# STPedal_Peripherals.net
KiCad netlist of a schematic drawn in Altium Designer
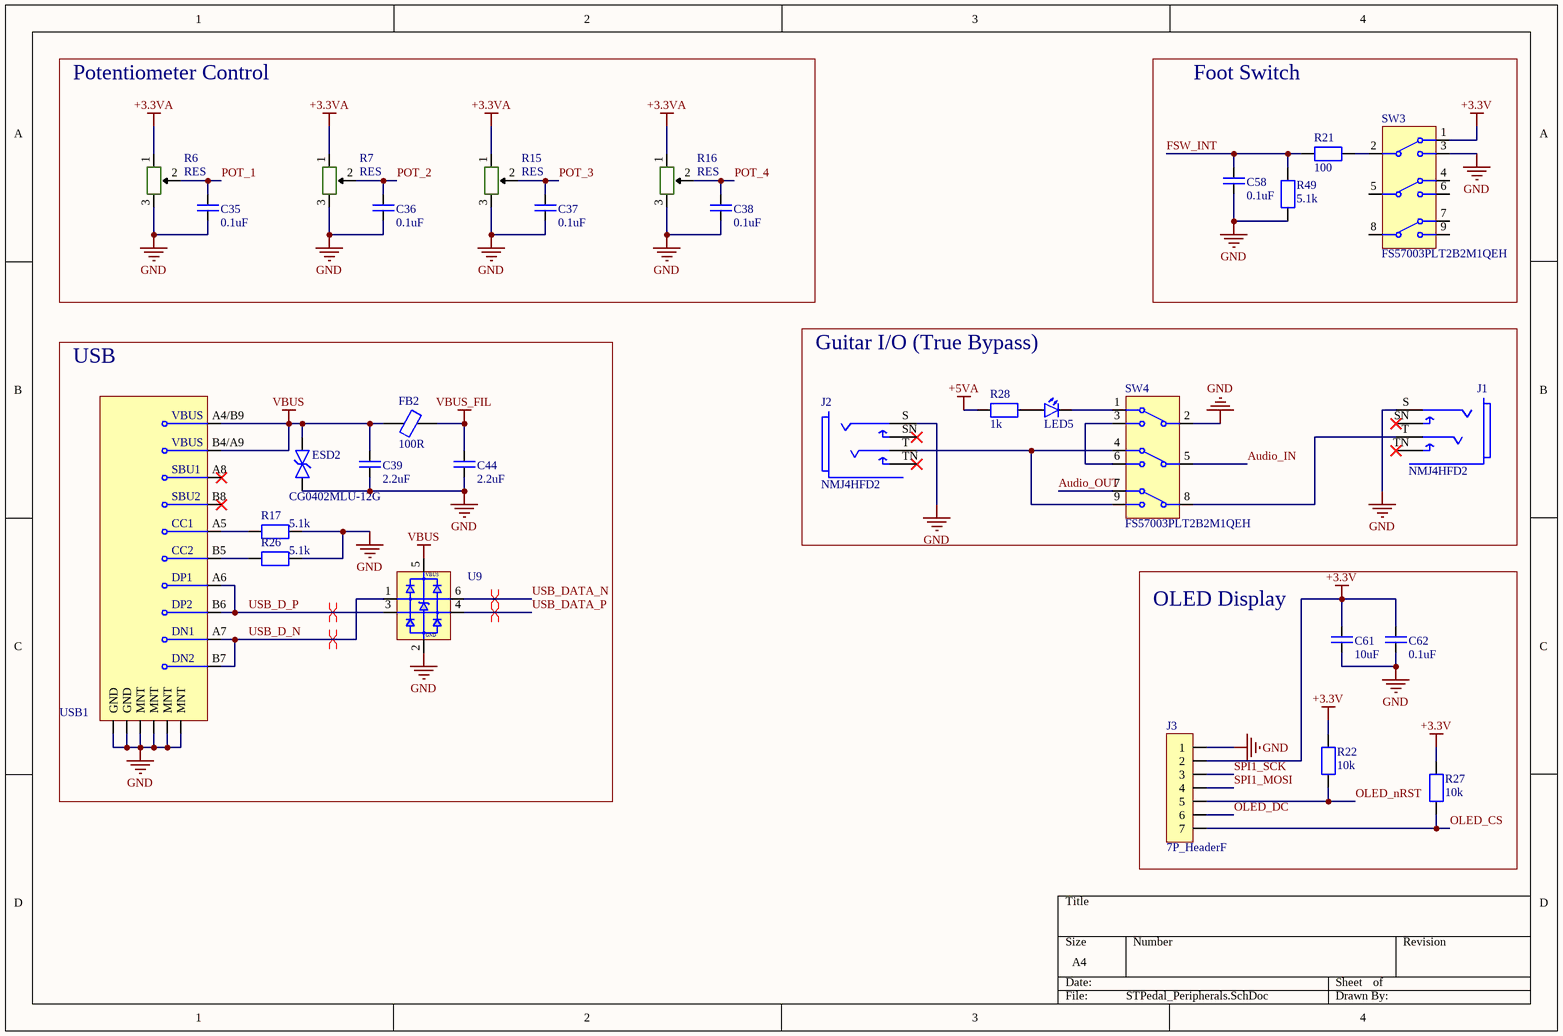
[diagram p0: STPedal_Peripherals.SchDoc]

(export (version "E")
  (design (tool "Eeschema 10.0.6"))
  (components
    (comp (ref "C35")
      (value "0.1uF")
      (footprint "CAPC_0402_1005X55N")
      (description "Capacitor 0402 - 0.1uF +-/10% / 16V")
      (fields
        (field (name "MANUFACTURER") "Samsung Electro-Mechanics")
        (field (name "MPN") "CL05B104KO5NNNC")
      )
      (libsource (lib "ReekoLib") (part "0.1uF_CAP_0402"))
    )
    (comp (ref "C36")
      (value "0.1uF")
      (footprint "CAPC_0402_1005X55N")
      (description "Capacitor 0402 - 0.1uF +-/10% / 16V")
      (fields
        (field (name "MANUFACTURER") "Samsung Electro-Mechanics")
        (field (name "MPN") "CL05B104KO5NNNC")
      )
      (libsource (lib "ReekoLib") (part "0.1uF_CAP_0402"))
    )
    (comp (ref "C37")
      (value "0.1uF")
      (footprint "CAPC_0402_1005X55N")
      (description "Capacitor 0402 - 0.1uF +-/10% / 16V")
      (fields
        (field (name "MANUFACTURER") "Samsung Electro-Mechanics")
        (field (name "MPN") "CL05B104KO5NNNC")
      )
      (libsource (lib "ReekoLib") (part "0.1uF_CAP_0402"))
    )
    (comp (ref "C38")
      (value "0.1uF")
      (footprint "CAPC_0402_1005X55N")
      (description "Capacitor 0402 - 0.1uF +-/10% / 16V")
      (fields
        (field (name "MANUFACTURER") "Samsung Electro-Mechanics")
        (field (name "MPN") "CL05B104KO5NNNC")
      )
      (libsource (lib "ReekoLib") (part "0.1uF_CAP_0402"))
    )
    (comp (ref "C39")
      (value "2.2uF")
      (footprint "CAPC_0402_1005X55N")
      (description "Capacitor 0402 - 2.2uF +-/10% / 25V")
      (fields
        (field (name "MANUFACTURER") "Samsung Electro-Mechanics")
        (field (name "MPN") "CL05A225MQ5NSNC")
      )
      (libsource (lib "ReekoLib") (part "2.2uF_CAP_0402"))
    )
    (comp (ref "C44")
      (value "2.2uF")
      (footprint "CAPC_0402_1005X55N")
      (description "Capacitor 0402 - 2.2uF +-/10% / 25V")
      (fields
        (field (name "MANUFACTURER") "Samsung Electro-Mechanics")
        (field (name "MPN") "CL05A225MQ5NSNC")
      )
      (libsource (lib "ReekoLib") (part "2.2uF_CAP_0402"))
    )
    (comp (ref "C58")
      (value "0.1uF")
      (footprint "CAPC_0402_1005X55N")
      (description "Capacitor 0402 - 0.1uF +-/10% / 16V")
      (fields
        (field (name "MANUFACTURER") "Samsung Electro-Mechanics")
        (field (name "MPN") "CL05B104KO5NNNC")
      )
      (libsource (lib "ReekoLib") (part "0.1uF_CAP_0402"))
    )
    (comp (ref "C61")
      (value "10uF")
      (footprint "RESC_0603_1608X55N")
      (description "Capacitor 0603 - 0.1uF +-/10% / 25V")
      (fields
        (field (name "MANUFACTURER") "Samsung Electro-Mechanics")
        (field (name "MPN") "CL10A106MA8NRNC")
      )
      (libsource (lib "ReekoLib") (part "10uF_CAP_0603"))
    )
    (comp (ref "C62")
      (value "0.1uF")
      (footprint "CAPC_0402_1005X55N")
      (description "Capacitor 0402 - 0.1uF +-/10% / 16V")
      (fields
        (field (name "MANUFACTURER") "Samsung Electro-Mechanics")
        (field (name "MPN") "CL05B104KO5NNNC")
      )
      (libsource (lib "ReekoLib") (part "0.1uF_CAP_0402"))
    )
    (comp (ref "ESD2")
      (value "CG0402MLU-12G")
      (footprint "DIOC_0402_1005X41N")
      (description "-40℃~+125℃ 0.05pF 1 12V 25V 5nA ESD IEC 61000-4-2 0402 ESD and Surge Protection (TVS/ESD) ROHS")
      (fields (field (name "MANUFACTURER") "BOURNS"))
      (libsource (lib "ReekoLib") (part "CG0402MLU-12G"))
    )
    (comp (ref "FB2")
      (value "100R")
      (footprint "FBC_0805_2012X105N")
      (fields (field (name "MANUFACTURER") "Sunlord") (field (name "MPN") "GZ2012D101TF"))
      (libsource (lib "ReekoLib") (part "100@100MHz_JLCFB_0805"))
    )
    (comp (ref "J1")
      (value "NMJ4HFD2")
      (footprint "FP-NMJ4HFD2-MFG")
      (description "Conn 1/4\" Mono Jack F 3 POS Solder RA Thru-Hole 3 Terminal 1 Port")
      (fields
        (field (name "MANUFACTURER") "Neutrik")
        (field (name "OCTOPART") "https://octopart.com/nmj4hfd2-neutrik-758952")
      )
      (libsource (lib "Altium Content Vault") (part "8c9933f05338f077543a5425baeefa5"))
    )
    (comp (ref "J2")
      (value "NMJ4HFD2")
      (footprint "FP-NMJ4HFD2-MFG")
      (description "Conn 1/4\" Mono Jack F 3 POS Solder RA Thru-Hole 3 Terminal 1 Port")
      (fields
        (field (name "MANUFACTURER") "Neutrik")
        (field (name "OCTOPART") "https://octopart.com/nmj4hfd2-neutrik-758952")
      )
      (libsource (lib "Altium Content Vault") (part "8c9933f05338f077543a5425baeefa5"))
    )
    (comp (ref "J3")
      (value "7P_HeaderF")
      (footprint "7P_2.54")
      (libsource (lib "ReekoLib") (part "7P_FemaleHeader_2.54mm"))
    )
    (comp (ref "LED5")
      (value "LED_5mm_THT")
      (footprint "LED_THT_5mm")
      (description "Generic THT 5mm led")
      (libsource (lib "ReekoLib") (part "LED_5mm_THT"))
    )
    (comp (ref "R6")
      (value "RES")
      (footprint "PTV09A-4020S-B104")
      (description "Generic Potentiometer 5mm pitch")
      (libsource (lib "ReekoLib") (part "POT_Gen_5mm"))
    )
    (comp (ref "R7")
      (value "RES")
      (footprint "PTV09A-4020S-B104")
      (description "Generic Potentiometer 5mm pitch")
      (libsource (lib "ReekoLib") (part "POT_Gen_5mm"))
    )
    (comp (ref "R15")
      (value "RES")
      (footprint "PTV09A-4020S-B104")
      (description "Generic Potentiometer 5mm pitch")
      (libsource (lib "ReekoLib") (part "POT_Gen_5mm"))
    )
    (comp (ref "R16")
      (value "RES")
      (footprint "PTV09A-4020S-B104")
      (description "Generic Potentiometer 5mm pitch")
      (libsource (lib "ReekoLib") (part "POT_Gen_5mm"))
    )
    (comp (ref "R17")
      (value "5.1k")
      (footprint "RESC_0402_1005X40N")
      (fields (field (name "MANUFACTURER") "UNI-ROYAL(Uniroyal Elec)") (field (name "MPN") "0402WGF5101TCE"))
      (libsource (lib "ReekoLib") (part "5.1k_JLCRES-0402"))
    )
    (comp (ref "R21")
      (value "100")
      (footprint "RESC_0402_1005X40N")
      (description "Resistor 0402 - 100R")
      (libsource (lib "ReekoLib") (part "100R_JLCRES-0402"))
    )
    (comp (ref "R22")
      (value "10k")
      (footprint "RESC_0402_1005X40N")
      (fields (field (name "MANUFACTURER") "UNI-ROYAL(Uniroyal Elec)") (field (name "MPN") "0402WGF1002TCE"))
      (libsource (lib "ReekoLib") (part "10k_JLCRES-0402"))
    )
    (comp (ref "R26")
      (value "5.1k")
      (footprint "RESC_0402_1005X40N")
      (fields (field (name "MANUFACTURER") "UNI-ROYAL(Uniroyal Elec)") (field (name "MPN") "0402WGF5101TCE"))
      (libsource (lib "ReekoLib") (part "5.1k_JLCRES-0402"))
    )
    (comp (ref "R27")
      (value "10k")
      (footprint "RESC_0402_1005X40N")
      (fields (field (name "MANUFACTURER") "UNI-ROYAL(Uniroyal Elec)") (field (name "MPN") "0402WGF1002TCE"))
      (libsource (lib "ReekoLib") (part "10k_JLCRES-0402"))
    )
    (comp (ref "R28")
      (value "1k")
      (footprint "RESC_0402_1005X40N")
      (description "Resistor 0402 - 1k")
      (fields (field (name "MANUFACTURER") "UNI-ROYAL(Uniroyal Elec)") (field (name "MPN") "0402WGF1001TCE"))
      (libsource (lib "ReekoLib") (part "1k_JLCRES-0402"))
    )
    (comp (ref "R49")
      (value "5.1k")
      (footprint "RESC_0402_1005X40N")
      (fields (field (name "MANUFACTURER") "UNI-ROYAL(Uniroyal Elec)") (field (name "MPN") "0402WGF5101TCE"))
      (libsource (lib "ReekoLib") (part "5.1k_JLCRES-0402"))
    )
    (comp (ref "SW3")
      (value "FS57003PLT2B2M1QEH")
      (footprint "3PDT_FootSwitch")
      (description "SWITCH PUSHBUTTON 3PDT 1A 9V")
      (fields (field (name "MANUFACTURER") "E-Switch"))
      (libsource (lib "ReekoLib") (part "FS57003PLT2B2M1QEH_FootSwitch_3PDT"))
    )
    (comp (ref "SW4")
      (value "FS57003PLT2B2M1QEH")
      (footprint "3PDT_FootSwitch")
      (description "SWITCH PUSHBUTTON 3PDT 1A 9V")
      (fields (field (name "MANUFACTURER") "E-Switch"))
      (libsource (lib "") (part "FS57003PLT2B2M1QEH_FootSwitch_3PDT_1"))
    )
    (comp (ref "U9")
      (value "USBLC6-2SC6_JLC")
      (footprint "SOT23-6L")
      (fields (field (name "MANUFACTURER") "STMicroelectronics") (field (name "MPN") "USBLC6-2SC6"))
      (libsource (lib "ReekoLib") (part "USBLC6-2SC6_JLC"))
    )
    (comp (ref "USB1")
      (value "USB_C_JLC_16P")
      (footprint "USB_C_SMT_16P")
      (fields (field (name "MANUFACTURER") "Korean Hroparts Elec") (field (name "MPN") "TYPE-C-31-M-12"))
      (libsource (lib "ReekoLib") (part "USB_C_JLC_16P"))
    )
  )
  (nets
    (net (code "1") (name "+3.3V") (class "Default")
      (node (ref "C61") (pin "2") (pintype "passive"))
      (node (ref "C62") (pin "2") (pintype "passive"))
      (node (ref "J3") (pin "2") (pinfunction "2_2") (pintype "passive"))
      (node (ref "R22") (pin "2") (pintype "passive"))
      (node (ref "R27") (pin "2") (pintype "passive"))
      (node (ref "SW3") (pin "1") (pintype "passive"))
    )
    (net (code "2") (name "+3.3VA") (class "Default")
      (node (ref "R15") (pin "1") (pintype "passive"))
      (node (ref "R16") (pin "1") (pintype "passive"))
      (node (ref "R6") (pin "1") (pintype "passive"))
      (node (ref "R7") (pin "1") (pintype "passive"))
    )
    (net (code "3") (name "+5VA") (class "Default") (node (ref "R28") (pin "1") (pintype "passive")))
    (net (code "4") (name "/Audio_IN") (class "Default") (node (ref "SW4") (pin "5") (pintype "passive")))
    (net (code "5") (name "/Audio_OUT") (class "Default") (node (ref "SW4") (pin "7") (pintype "passive")))
    (net (code "6") (name "/FSW_INT") (class "Default")
      (node (ref "C58") (pin "2") (pintype "passive"))
      (node (ref "R21") (pin "1") (pintype "passive"))
      (node (ref "R49") (pin "2") (pintype "passive"))
    )
    (net (code "7") (name "/OLED_CS") (class "Default")
      (node (ref "J3") (pin "7") (pinfunction "7_7") (pintype "passive"))
      (node (ref "R27") (pin "1") (pintype "passive"))
    )
    (net (code "8") (name "/OLED_DC") (class "Default")
      (node (ref "J3") (pin "6") (pinfunction "6_6") (pintype "passive"))
    )
    (net (code "9") (name "/OLED_nRST") (class "Default")
      (node (ref "J3") (pin "5") (pinfunction "5_5") (pintype "passive"))
      (node (ref "R22") (pin "1") (pintype "passive"))
    )
    (net (code "10") (name "/POT_1") (class "Default")
      (node (ref "C35") (pin "2") (pintype "passive"))
      (node (ref "R6") (pin "2") (pintype "passive"))
    )
    (net (code "11") (name "/POT_2") (class "Default")
      (node (ref "C36") (pin "2") (pintype "passive"))
      (node (ref "R7") (pin "2") (pintype "passive"))
    )
    (net (code "12") (name "/POT_3") (class "Default")
      (node (ref "C37") (pin "2") (pintype "passive"))
      (node (ref "R15") (pin "2") (pintype "passive"))
    )
    (net (code "13") (name "/POT_4") (class "Default")
      (node (ref "C38") (pin "2") (pintype "passive"))
      (node (ref "R16") (pin "2") (pintype "passive"))
    )
    (net (code "14") (name "/SPI1_MOSI") (class "Default")
      (node (ref "J3") (pin "4") (pinfunction "4_4") (pintype "passive"))
    )
    (net (code "15") (name "/SPI1_SCK") (class "Default")
      (node (ref "J3") (pin "3") (pinfunction "3_3") (pintype "passive"))
    )
    (net (code "16") (name "/USB_DATA_N") (class "Default") (node (ref "U9") (pin "6") (pintype "passive")))
    (net (code "17") (name "/USB_DATA_P") (class "Default") (node (ref "U9") (pin "4") (pintype "passive")))
    (net (code "18") (name "/USB_D_N") (class "Default")
      (node (ref "U9") (pin "1") (pintype "passive"))
      (node (ref "USB1") (pin "A7") (pinfunction "DN1_A7") (pintype "passive"))
      (node (ref "USB1") (pin "B7") (pinfunction "DN2_B7") (pintype "passive"))
    )
    (net (code "19") (name "/USB_D_P") (class "Default")
      (node (ref "U9") (pin "3") (pintype "passive"))
      (node (ref "USB1") (pin "A6") (pinfunction "DP1_A6") (pintype "passive"))
      (node (ref "USB1") (pin "B6") (pinfunction "DP2_B6") (pintype "passive"))
    )
    (net (code "20") (name "GND") (class "Default")
      (node (ref "C35") (pin "1") (pintype "passive"))
      (node (ref "C36") (pin "1") (pintype "passive"))
      (node (ref "C37") (pin "1") (pintype "passive"))
      (node (ref "C38") (pin "1") (pintype "passive"))
      (node (ref "C39") (pin "1") (pintype "passive"))
      (node (ref "C44") (pin "1") (pintype "passive"))
      (node (ref "C58") (pin "1") (pintype "passive"))
      (node (ref "C61") (pin "1") (pintype "passive"))
      (node (ref "C62") (pin "1") (pintype "passive"))
      (node (ref "ESD2") (pin "1") (pintype "passive"))
      (node (ref "J1") (pin "S") (pinfunction "S_S") (pintype "passive"))
      (node (ref "J2") (pin "S") (pinfunction "S_S") (pintype "passive"))
      (node (ref "J3") (pin "1") (pinfunction "1_1") (pintype "passive"))
      (node (ref "R15") (pin "3") (pintype "passive"))
      (node (ref "R16") (pin "3") (pintype "passive"))
      (node (ref "R17") (pin "2") (pintype "passive"))
      (node (ref "R26") (pin "2") (pintype "passive"))
      (node (ref "R49") (pin "1") (pintype "passive"))
      (node (ref "R6") (pin "3") (pintype "passive"))
      (node (ref "R7") (pin "3") (pintype "passive"))
      (node (ref "SW3") (pin "3") (pintype "passive"))
      (node (ref "SW4") (pin "2") (pintype "passive"))
      (node (ref "U9") (pin "2") (pintype "passive"))
      (node (ref "USB1") (pin "A1/B12") (pinfunction "GND_A1/B12") (pintype "passive"))
      (node (ref "USB1") (pin "B1/A12") (pinfunction "GND_B1/A12") (pintype "passive"))
      (node (ref "USB1") (pin "MNT1") (pinfunction "MNT_MNT1") (pintype "passive"))
      (node (ref "USB1") (pin "MNT2") (pinfunction "MNT_MNT2") (pintype "passive"))
      (node (ref "USB1") (pin "MNT3") (pinfunction "MNT_MNT3") (pintype "passive"))
      (node (ref "USB1") (pin "MNT4") (pinfunction "MNT_MNT4") (pintype "passive"))
    )
    (net (code "21") (name "Net-(J1-PadT)") (class "Default")
      (node (ref "J1") (pin "T") (pinfunction "T_T") (pintype "passive"))
      (node (ref "SW4") (pin "8") (pintype "passive"))
    )
    (net (code "22") (name "Net-(J2-PadT)") (class "Default")
      (node (ref "J2") (pin "T") (pinfunction "T_T") (pintype "passive"))
      (node (ref "SW4") (pin "4") (pintype "passive"))
      (node (ref "SW4") (pin "9") (pintype "passive"))
    )
    (net (code "23") (name "Net-(LED5-Pad1)") (class "Default")
      (node (ref "LED5") (pin "1") (pintype "passive"))
      (node (ref "R28") (pin "2") (pintype "passive"))
    )
    (net (code "24") (name "Net-(LED5-Pad2)") (class "Default")
      (node (ref "LED5") (pin "2") (pintype "passive"))
      (node (ref "SW4") (pin "1") (pintype "passive"))
    )
    (net (code "25") (name "Net-(R21-Pad2)") (class "Default")
      (node (ref "R21") (pin "2") (pintype "passive"))
      (node (ref "SW3") (pin "2") (pintype "passive"))
    )
    (net (code "26") (name "Net-(SW4-Pad3)") (class "Default")
      (node (ref "SW4") (pin "3") (pintype "passive"))
      (node (ref "SW4") (pin "6") (pintype "passive"))
    )
    (net (code "27") (name "Net-(USB1-CC1)") (class "Default")
      (node (ref "R17") (pin "1") (pintype "passive"))
      (node (ref "USB1") (pin "A5") (pinfunction "CC1_A5") (pintype "passive"))
    )
    (net (code "28") (name "Net-(USB1-CC2)") (class "Default")
      (node (ref "R26") (pin "1") (pintype "passive"))
      (node (ref "USB1") (pin "B5") (pinfunction "CC2_B5") (pintype "passive"))
    )
    (net (code "29") (name "VBUS") (class "Default")
      (node (ref "C39") (pin "2") (pintype "passive"))
      (node (ref "ESD2") (pin "2") (pintype "passive"))
      (node (ref "FB2") (pin "1") (pintype "passive"))
      (node (ref "U9") (pin "5") (pintype "passive"))
      (node (ref "USB1") (pin "A4/B9") (pinfunction "VBUS_A4/B9") (pintype "passive"))
      (node (ref "USB1") (pin "B4/A9") (pinfunction "VBUS_B4/A9") (pintype "passive"))
    )
    (net (code "30") (name "VBUS_FIL") (class "Default")
      (node (ref "C44") (pin "2") (pintype "passive"))
      (node (ref "FB2") (pin "2") (pintype "passive"))
    )
    (net (code "31") (name "unconnected-(J1-PadSN)") (class "Default")
      (node (ref "J1") (pin "SN") (pinfunction "SN_SN") (pintype "passive+no_connect"))
    )
    (net (code "32") (name "unconnected-(J1-PadTN)") (class "Default")
      (node (ref "J1") (pin "TN") (pinfunction "TN_TN") (pintype "passive+no_connect"))
    )
    (net (code "33") (name "unconnected-(J2-PadSN)") (class "Default")
      (node (ref "J2") (pin "SN") (pinfunction "SN_SN") (pintype "passive+no_connect"))
    )
    (net (code "34") (name "unconnected-(J2-PadTN)") (class "Default")
      (node (ref "J2") (pin "TN") (pinfunction "TN_TN") (pintype "passive+no_connect"))
    )
    (net (code "35") (name "unconnected-(SW3-Pad4)") (class "Default")
      (node (ref "SW3") (pin "4") (pintype "passive"))
    )
    (net (code "36") (name "unconnected-(SW3-Pad5)") (class "Default")
      (node (ref "SW3") (pin "5") (pintype "passive"))
    )
    (net (code "37") (name "unconnected-(SW3-Pad6)") (class "Default")
      (node (ref "SW3") (pin "6") (pintype "passive"))
    )
    (net (code "38") (name "unconnected-(SW3-Pad7)") (class "Default")
      (node (ref "SW3") (pin "7") (pintype "passive"))
    )
    (net (code "39") (name "unconnected-(SW3-Pad8)") (class "Default")
      (node (ref "SW3") (pin "8") (pintype "passive"))
    )
    (net (code "40") (name "unconnected-(SW3-Pad9)") (class "Default")
      (node (ref "SW3") (pin "9") (pintype "passive"))
    )
    (net (code "41") (name "unconnected-(USB1-SBU1-PadA8)") (class "Default")
      (node (ref "USB1") (pin "A8") (pinfunction "SBU1_A8") (pintype "passive+no_connect"))
    )
    (net (code "42") (name "unconnected-(USB1-SBU2-PadB8)") (class "Default")
      (node (ref "USB1") (pin "B8") (pinfunction "SBU2_B8") (pintype "passive+no_connect"))
    )
  )
)
